# motorEncoder.net
KiCad netlist of a schematic drawn in Altium Designer
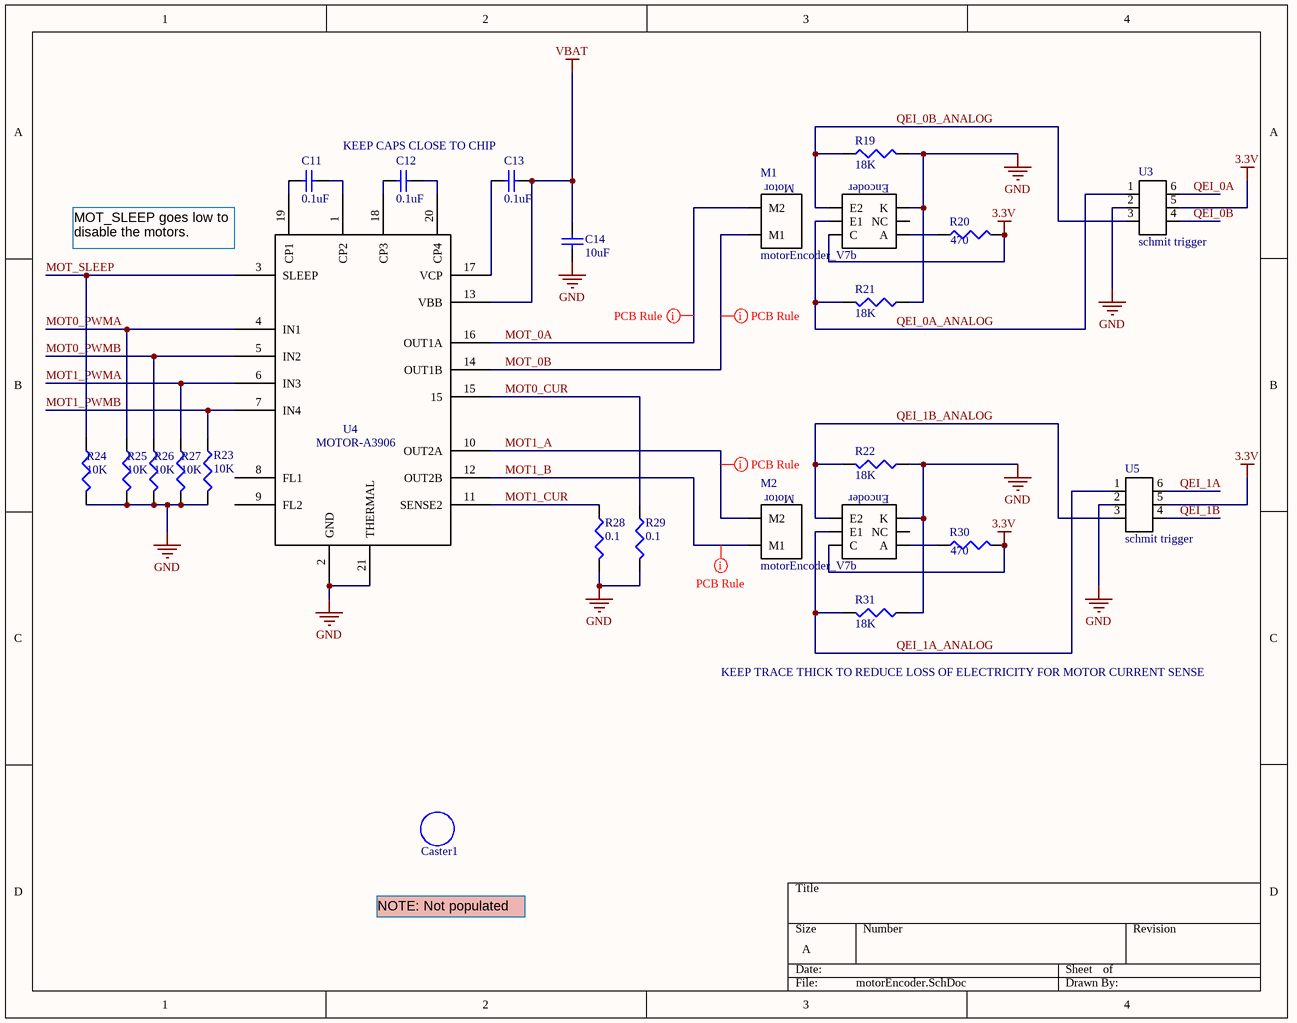
[diagram p0: motorEncoder.SchDoc]

(export (version "E")
  (design (tool "Eeschema 10.0.6"))
  (components
    (comp (ref "C11")
      (value "0.1uF")
      (footprint "CAPC1005L")
      (description "Capacitor (Semiconductor SIM Model)")
      (fields (field (name "Comment") "Cap Semi") (field (name "PUBLISHER") "Altium Limited"))
      (libsource (lib "Miscellaneous Devices") (part "Cap Semi"))
    )
    (comp (ref "C12")
      (value "0.1uF")
      (footprint "CAPC1005L")
      (description "Capacitor (Semiconductor SIM Model)")
      (fields (field (name "Comment") "Cap Semi") (field (name "PUBLISHER") "Altium Limited"))
      (libsource (lib "Miscellaneous Devices") (part "Cap Semi"))
    )
    (comp (ref "C13")
      (value "0.1uF")
      (footprint "CAPC1005L")
      (description "Capacitor (Semiconductor SIM Model)")
      (fields (field (name "Comment") "Cap Semi") (field (name "PUBLISHER") "Altium Limited"))
      (libsource (lib "Miscellaneous Devices") (part "Cap Semi"))
    )
    (comp (ref "C14")
      (value "10uF")
      (footprint "CAPC1608L")
      (description "Capacitor (Semiconductor SIM Model)")
      (fields (field (name "Comment") "Cap Semi") (field (name "PUBLISHER") "Altium Limited"))
      (libsource (lib "Miscellaneous Devices") (part "Cap Semi"))
    )
    (comp (ref "Caster1")
      (value "non connect")
      (footprint "3/4\"CASTER2")
      (description "This is just a space saver to get the caster onto the pcb")
      (libsource (lib "mrone") (part "Caster 3/4in"))
    )
    (comp (ref "M1")
      (value "motorEncoder_V7b")
      (footprint "motorEncoder_V7b")
      (libsource (lib "mrone") (part "motorEncoder_V7b"))
    )
    (comp (ref "M2")
      (value "motorEncoder_V7b")
      (footprint "motorEncoder_V7b")
      (libsource (lib "mrone") (part "motorEncoder_V7b"))
    )
    (comp (ref "R19")
      (value "18K")
      (footprint "RESC1608L")
      (description "Resistor")
      (fields (field (name "PUBLISHER") "Altium Limited"))
      (libsource (lib "Miscellaneous Devices") (part "Res3"))
    )
    (comp (ref "R20")
      (value "470")
      (footprint "RESC1608L")
      (description "Resistor")
      (fields (field (name "PUBLISHER") "Altium Limited"))
      (libsource (lib "Miscellaneous Devices") (part "Res3"))
    )
    (comp (ref "R21")
      (value "18K")
      (footprint "RESC1608L")
      (description "Resistor")
      (fields (field (name "PUBLISHER") "Altium Limited"))
      (libsource (lib "Miscellaneous Devices") (part "Res3"))
    )
    (comp (ref "R22")
      (value "18K")
      (footprint "RESC1608L")
      (description "Resistor")
      (fields (field (name "PUBLISHER") "Altium Limited"))
      (libsource (lib "Miscellaneous Devices") (part "Res3"))
    )
    (comp (ref "R23")
      (value "10K")
      (footprint "RESC1608L")
      (description "Resistor")
      (fields (field (name "Comment") "Res3") (field (name "PUBLISHER") "Altium Limited"))
      (libsource (lib "Miscellaneous Devices") (part "Res3"))
    )
    (comp (ref "R24")
      (value "10K")
      (footprint "CAPC1608L")
      (description "Resistor")
      (fields (field (name "Comment") "Res3") (field (name "PUBLISHER") "Altium Limited"))
      (libsource (lib "Miscellaneous Devices") (part "Res3"))
    )
    (comp (ref "R25")
      (value "10K")
      (footprint "RESC1608L")
      (description "Resistor")
      (fields (field (name "Comment") "Res3") (field (name "PUBLISHER") "Altium Limited"))
      (libsource (lib "Miscellaneous Devices") (part "Res3"))
    )
    (comp (ref "R26")
      (value "10K")
      (footprint "RESC1608L")
      (description "Resistor")
      (fields (field (name "Comment") "Res3") (field (name "PUBLISHER") "Altium Limited"))
      (libsource (lib "Miscellaneous Devices") (part "Res3"))
    )
    (comp (ref "R27")
      (value "10K")
      (footprint "RESC1608L")
      (description "Resistor")
      (fields (field (name "Comment") "Res3") (field (name "PUBLISHER") "Altium Limited"))
      (libsource (lib "Miscellaneous Devices") (part "Res3"))
    )
    (comp (ref "R28")
      (value "0.1")
      (footprint "RESC1608L")
      (description "Resistor")
      (fields (field (name "Comment") "Res3") (field (name "PUBLISHER") "Altium Limited"))
      (libsource (lib "Miscellaneous Devices") (part "Res3"))
    )
    (comp (ref "R29")
      (value "0.1")
      (footprint "RESC1608L")
      (description "Resistor")
      (fields (field (name "Comment") "Res3") (field (name "PUBLISHER") "Altium Limited"))
      (libsource (lib "Miscellaneous Devices") (part "Res3"))
    )
    (comp (ref "R30")
      (value "470")
      (footprint "RESC1608L")
      (description "Resistor")
      (fields (field (name "PUBLISHER") "Altium Limited"))
      (libsource (lib "Miscellaneous Devices") (part "Res3"))
    )
    (comp (ref "R31")
      (value "18K")
      (footprint "RESC1608L")
      (description "Resistor")
      (fields (field (name "PUBLISHER") "Altium Limited"))
      (libsource (lib "Miscellaneous Devices") (part "Res3"))
    )
    (comp (ref "U3")
      (value "schmit trigger")
      (footprint "DCK(R-PDSO-C6)")
      (libsource (lib "mrone") (part "schmit trigger"))
    )
    (comp (ref "U4")
      (value "MOTOR-A3906")
      (footprint "QFN-20")
      (libsource (lib "V2_altium") (part "MOTOR-A3906"))
    )
    (comp (ref "U5")
      (value "schmit trigger")
      (footprint "DCK(R-PDSO-C6)")
      (libsource (lib "mrone") (part "schmit trigger"))
    )
  )
  (nets
    (net (code "2") (name "/MOT0_CUR") (class "Default")
      (node (ref "R29") (pin "1") (pinfunction "1_1") (pintype "passive"))
      (node (ref "U4") (pin "15") (pinfunction "15_15") (pintype "passive"))
    )
    (net (code "3") (name "/MOT0_PWMA") (class "Default")
      (node (ref "R25") (pin "1") (pinfunction "1_1") (pintype "passive"))
      (node (ref "U4") (pin "4") (pinfunction "IN1_4") (pintype "passive"))
    )
    (net (code "4") (name "/MOT0_PWMB") (class "Default")
      (node (ref "R26") (pin "1") (pinfunction "1_1") (pintype "passive"))
      (node (ref "U4") (pin "5") (pinfunction "IN2_5") (pintype "passive"))
    )
    (net (code "5") (name "/MOT1_A") (class "Default")
      (node (ref "M2") (pin "M2") (pinfunction "M2_M2") (pintype "passive"))
      (node (ref "U4") (pin "10") (pinfunction "OUT2A_10") (pintype "passive"))
    )
    (net (code "6") (name "/MOT1_B") (class "Default")
      (node (ref "M2") (pin "M1") (pinfunction "M1_M1") (pintype "passive"))
      (node (ref "U4") (pin "12") (pinfunction "OUT2B_12") (pintype "passive"))
    )
    (net (code "7") (name "/MOT1_CUR") (class "Default")
      (node (ref "R28") (pin "1") (pinfunction "1_1") (pintype "passive"))
      (node (ref "U4") (pin "11") (pinfunction "SENSE2_11") (pintype "passive"))
    )
    (net (code "8") (name "/MOT1_PWMA") (class "Default")
      (node (ref "R27") (pin "1") (pinfunction "1_1") (pintype "passive"))
      (node (ref "U4") (pin "6") (pinfunction "IN3_6") (pintype "passive"))
    )
    (net (code "9") (name "/MOT1_PWMB") (class "Default")
      (node (ref "R23") (pin "1") (pinfunction "1_1") (pintype "passive"))
      (node (ref "U4") (pin "7") (pinfunction "IN4_7") (pintype "passive"))
    )
    (net (code "10") (name "/MOT_0A") (class "Default")
      (node (ref "M1") (pin "M2") (pinfunction "M2_M2") (pintype "passive"))
      (node (ref "U4") (pin "16") (pinfunction "OUT1A_16") (pintype "passive"))
    )
    (net (code "11") (name "/MOT_0B") (class "Default")
      (node (ref "M1") (pin "M1") (pinfunction "M1_M1") (pintype "passive"))
      (node (ref "U4") (pin "14") (pinfunction "OUT1B_14") (pintype "passive"))
    )
    (net (code "12") (name "/MOT_SLEEP") (class "Default")
      (node (ref "R24") (pin "1") (pinfunction "1_1") (pintype "passive"))
      (node (ref "U4") (pin "3") (pinfunction "SLEEP_3") (pintype "passive"))
    )
    (net (code "13") (name "/QEI_0A") (class "Default")
      (node (ref "U3") (pin "6") (pinfunction "4_6") (pintype "passive"))
    )
    (net (code "14") (name "/QEI_0A_ANALOG") (class "Default")
      (node (ref "M1") (pin "E1") (pinfunction "E1_E1") (pintype "passive"))
      (node (ref "R21") (pin "2") (pinfunction "2_2") (pintype "passive"))
      (node (ref "U3") (pin "1") (pinfunction "1_1") (pintype "passive"))
    )
    (net (code "15") (name "/QEI_0B") (class "Default")
      (node (ref "U3") (pin "4") (pinfunction "4_4") (pintype "passive"))
    )
    (net (code "16") (name "/QEI_0B_ANALOG") (class "Default")
      (node (ref "M1") (pin "E2") (pinfunction "E2_E2") (pintype "passive"))
      (node (ref "R19") (pin "1") (pinfunction "1_1") (pintype "passive"))
      (node (ref "U3") (pin "3") (pinfunction "3_3") (pintype "passive"))
    )
    (net (code "17") (name "/QEI_1A") (class "Default")
      (node (ref "U5") (pin "6") (pinfunction "4_6") (pintype "passive"))
    )
    (net (code "18") (name "/QEI_1A_ANALOG") (class "Default")
      (node (ref "M2") (pin "E1") (pinfunction "E1_E1") (pintype "passive"))
      (node (ref "R31") (pin "2") (pinfunction "2_2") (pintype "passive"))
      (node (ref "U5") (pin "1") (pinfunction "1_1") (pintype "passive"))
    )
    (net (code "19") (name "/QEI_1B") (class "Default")
      (node (ref "U5") (pin "4") (pinfunction "4_4") (pintype "passive"))
    )
    (net (code "20") (name "/QEI_1B_ANALOG") (class "Default")
      (node (ref "M2") (pin "E2") (pinfunction "E2_E2") (pintype "passive"))
      (node (ref "R22") (pin "2") (pinfunction "2_2") (pintype "passive"))
      (node (ref "U5") (pin "3") (pinfunction "3_3") (pintype "passive"))
    )
    (net (code "21") (name "3.3V") (class "Default")
      (node (ref "M1") (pin "C") (pinfunction "C_C") (pintype "passive"))
      (node (ref "M2") (pin "C") (pinfunction "C_C") (pintype "passive"))
      (node (ref "R20") (pin "2") (pinfunction "2_2") (pintype "passive"))
      (node (ref "R30") (pin "2") (pinfunction "2_2") (pintype "passive"))
      (node (ref "U3") (pin "5") (pinfunction "5_5") (pintype "passive"))
      (node (ref "U5") (pin "5") (pinfunction "5_5") (pintype "passive"))
    )
    (net (code "22") (name "GND") (class "Default")
      (node (ref "C14") (pin "1") (pinfunction "1_1") (pintype "passive"))
      (node (ref "M1") (pin "K") (pinfunction "K_K") (pintype "passive"))
      (node (ref "M2") (pin "K") (pinfunction "K_K") (pintype "passive"))
      (node (ref "R19") (pin "2") (pinfunction "2_2") (pintype "passive"))
      (node (ref "R21") (pin "1") (pinfunction "1_1") (pintype "passive"))
      (node (ref "R22") (pin "1") (pinfunction "1_1") (pintype "passive"))
      (node (ref "R23") (pin "2") (pinfunction "2_2") (pintype "passive"))
      (node (ref "R24") (pin "2") (pinfunction "2_2") (pintype "passive"))
      (node (ref "R25") (pin "2") (pinfunction "2_2") (pintype "passive"))
      (node (ref "R26") (pin "2") (pinfunction "2_2") (pintype "passive"))
      (node (ref "R27") (pin "2") (pinfunction "2_2") (pintype "passive"))
      (node (ref "R28") (pin "2") (pinfunction "2_2") (pintype "passive"))
      (node (ref "R29") (pin "2") (pinfunction "2_2") (pintype "passive"))
      (node (ref "R31") (pin "1") (pinfunction "1_1") (pintype "passive"))
      (node (ref "U3") (pin "2") (pinfunction "2_2") (pintype "passive"))
      (node (ref "U4") (pin "2") (pinfunction "GND_2") (pintype "passive"))
      (node (ref "U4") (pin "21") (pinfunction "THERMAL_21") (pintype "passive"))
      (node (ref "U5") (pin "2") (pinfunction "2_2") (pintype "passive"))
    )
    (net (code "23") (name "Net-(M1-PadA)") (class "Default")
      (node (ref "M1") (pin "A") (pinfunction "A_A") (pintype "passive"))
      (node (ref "R20") (pin "1") (pinfunction "1_1") (pintype "passive"))
    )
    (net (code "24") (name "Net-(M2-PadA)") (class "Default")
      (node (ref "M2") (pin "A") (pinfunction "A_A") (pintype "passive"))
      (node (ref "R30") (pin "1") (pinfunction "1_1") (pintype "passive"))
    )
    (net (code "25") (name "Net-(U4-CP1)") (class "Default")
      (node (ref "C11") (pin "1") (pinfunction "1_1") (pintype "passive"))
      (node (ref "U4") (pin "19") (pinfunction "CP1_19") (pintype "passive"))
    )
    (net (code "26") (name "Net-(U4-CP2)") (class "Default")
      (node (ref "C11") (pin "2") (pinfunction "2_2") (pintype "passive"))
      (node (ref "U4") (pin "1") (pinfunction "CP2_1") (pintype "passive"))
    )
    (net (code "27") (name "Net-(U4-CP3)") (class "Default")
      (node (ref "C12") (pin "1") (pinfunction "1_1") (pintype "passive"))
      (node (ref "U4") (pin "18") (pinfunction "CP3_18") (pintype "passive"))
    )
    (net (code "28") (name "Net-(U4-CP4)") (class "Default")
      (node (ref "C12") (pin "2") (pinfunction "2_2") (pintype "passive"))
      (node (ref "U4") (pin "20") (pinfunction "CP4_20") (pintype "passive"))
    )
    (net (code "29") (name "Net-(U4-VCP)") (class "Default")
      (node (ref "C13") (pin "2") (pinfunction "2_2") (pintype "passive"))
      (node (ref "U4") (pin "17") (pinfunction "VCP_17") (pintype "passive"))
    )
    (net (code "30") (name "VBAT") (class "Default")
      (node (ref "C13") (pin "1") (pinfunction "1_1") (pintype "passive"))
      (node (ref "C14") (pin "2") (pinfunction "2_2") (pintype "passive"))
      (node (ref "U4") (pin "13") (pinfunction "VBB_13") (pintype "passive"))
    )
    (net (code "31") (name "unconnected-(M1-PadNC)") (class "Default")
      (node (ref "M1") (pin "NC") (pinfunction "NC_NC") (pintype "passive"))
    )
    (net (code "32") (name "unconnected-(M2-PadNC)") (class "Default")
      (node (ref "M2") (pin "NC") (pinfunction "NC_NC") (pintype "passive"))
    )
    (net (code "33") (name "unconnected-(U4-FL1-Pad8)") (class "Default")
      (node (ref "U4") (pin "8") (pinfunction "FL1_8") (pintype "passive"))
    )
    (net (code "34") (name "unconnected-(U4-FL2-Pad9)") (class "Default")
      (node (ref "U4") (pin "9") (pinfunction "FL2_9") (pintype "passive"))
    )
  )
)
